# 03_ICs.net
KiCad netlist of a schematic drawn in Altium Designer
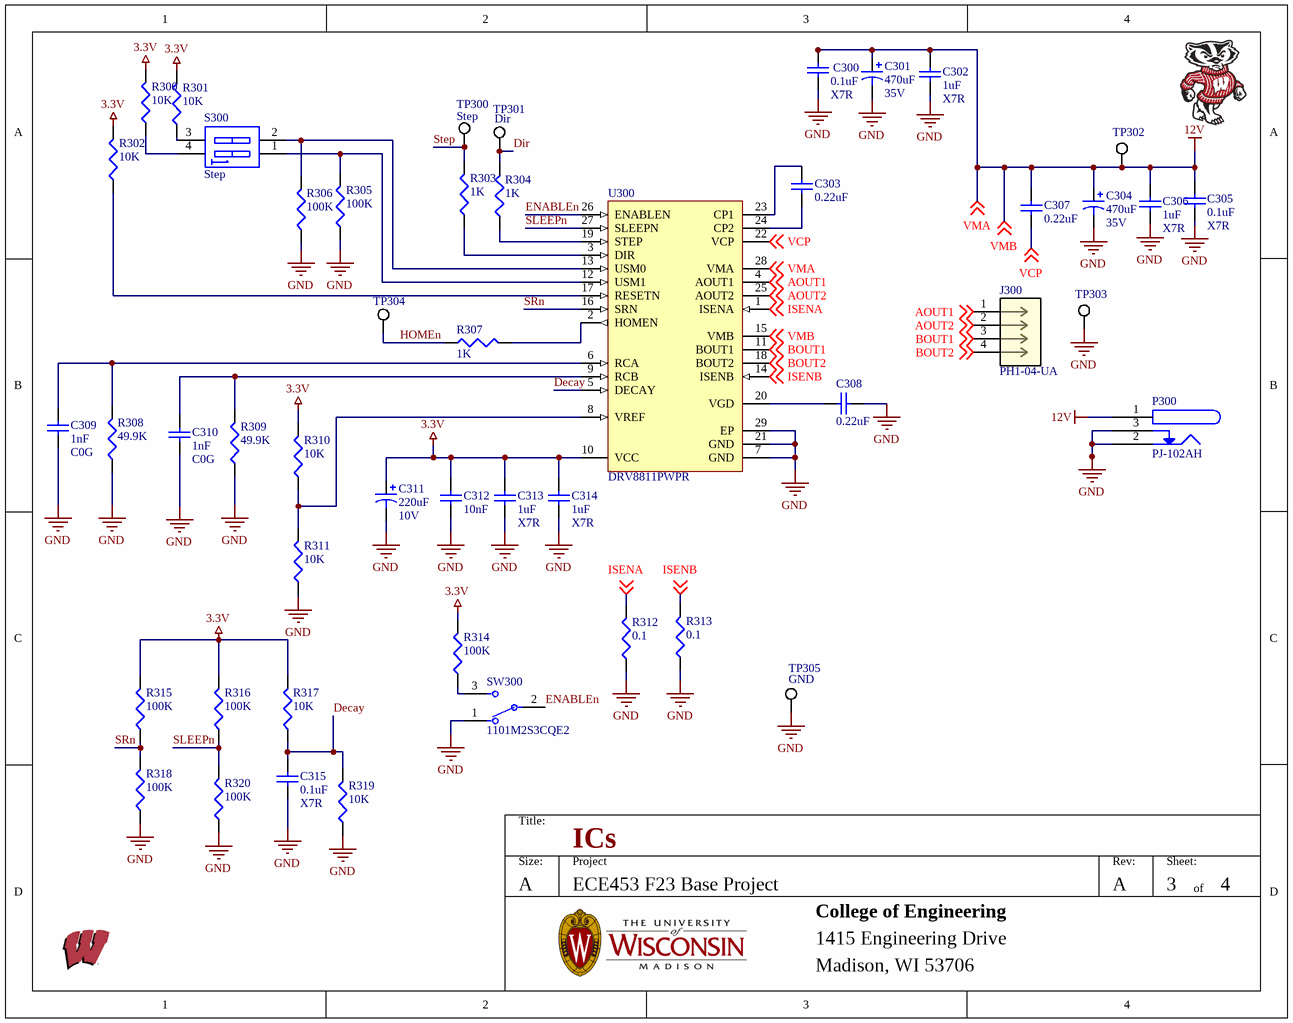
[diagram p0: 03_ICs.SchDoc]

(export (version "E")
  (design (tool "Eeschema 10.0.6"))
  (components
    (comp (ref "C300")
      (value "0.1uF")
      (footprint "CAPC2012M")
      (description "Cap Ceramic 0.1uF 50V X7R 20% SMD 0805 125°C Plastic T/R")
      (fields
        (field (name "MANUFACTURER") "KEMET")
        (field (name "MANUFACTURER PART NUMBER") "C0805C104M5RAC7210")
        (field (name "DIELECTRIC") "X7R")
      )
      (libsource (lib "ECE453") (part "Cap_1"))
    )
    (comp (ref "C301")
      (value "470uF")
      (footprint "CAPPR5-10x12.5")
      (description "CAP ALUM 470UF 20% 35V RADIAL")
      (fields
        (field (name "VOLTAGE") "35V")
        (field (name "MANUFACTURER") "Rubycon")
        (field (name "TOLERANCE") "20%")
      )
      (libsource (lib "ECE453") (part "Cap Pol3_1"))
    )
    (comp (ref "C302")
      (value "1uF")
      (footprint "CAPC2012M")
      (description "CAP CER 1UF 50V X7R 0805")
      (fields
        (field (name "MANUFACTURER") "Samsung")
        (field (name "MANUFACTURER PART NUMBER") "CL21B105KBFNNNE")
        (field (name "DIELECTRIC") "X7R")
      )
      (libsource (lib "ECE453") (part "Cap"))
    )
    (comp (ref "C303")
      (value "0.22uF")
      (footprint "CAP_0805")
      (description "Cap Ceramic 0.22uF 50V X7R 10% SMD 0805 125°C Plastic T/R")
      (fields
        (field (name "MANUFACTURER") "KEMET")
        (field (name "MANUFACTURER PART NUMBER") "C0805C224K5RACAUTO7210")
      )
      (libsource (lib "ECE453") (part "Cap_2"))
    )
    (comp (ref "C304")
      (value "470uF")
      (footprint "CAPPR5-10x12.5")
      (description "CAP ALUM 470UF 20% 35V RADIAL")
      (fields
        (field (name "VOLTAGE") "35V")
        (field (name "MANUFACTURER") "Rubycon")
        (field (name "TOLERANCE") "20%")
      )
      (libsource (lib "ECE453") (part "Cap Pol3_1"))
    )
    (comp (ref "C305")
      (value "0.1uF")
      (footprint "CAPC2012M")
      (description "Cap Ceramic 0.1uF 50V X7R 20% SMD 0805 125°C Plastic T/R")
      (fields
        (field (name "MANUFACTURER") "KEMET")
        (field (name "MANUFACTURER PART NUMBER") "C0805C104M5RAC7210")
        (field (name "DIELECTRIC") "X7R")
      )
      (libsource (lib "ECE453") (part "Cap_1"))
    )
    (comp (ref "C306")
      (value "1uF")
      (footprint "CAPC2012M")
      (description "CAP CER 1UF 50V X7R 0805")
      (fields
        (field (name "MANUFACTURER") "Samsung")
        (field (name "MANUFACTURER PART NUMBER") "CL21B105KBFNNNE")
        (field (name "DIELECTRIC") "X7R")
      )
      (libsource (lib "ECE453") (part "Cap"))
    )
    (comp (ref "C307")
      (value "0.22uF")
      (footprint "CAPC2012M")
      (description "Cap Ceramic 0.22uF 50V X7R 10% SMD 0805 125°C Plastic T/R")
      (fields
        (field (name "MANUFACTURER") "KEMET")
        (field (name "MANUFACTURER PART NUMBER") "C0805C224K5RACAUTO7210")
      )
      (libsource (lib "ECE453") (part "Cap_2"))
    )
    (comp (ref "C308")
      (value "0.22uF")
      (footprint "CAP_0805")
      (description "Cap Ceramic 0.22uF 50V X7R 10% SMD 0805 125°C Plastic T/R")
      (fields
        (field (name "MANUFACTURER") "KEMET")
        (field (name "MANUFACTURER PART NUMBER") "C0805C224K5RACAUTO7210")
      )
      (libsource (lib "ECE453") (part "Cap_2"))
    )
    (comp (ref "C309")
      (value "1nF")
      (footprint "CAP_0805")
      (description "Cap Ceramic 0.001uF 50V C0G 5% SMD 0805 125°C Punched Paper T/R")
      (fields
        (field (name "MANUFACTURER") "KEMET")
        (field (name "MANUFACTURER PART NUMBER") "C0805C102J5GAC7210")
        (field (name "DIELECTRIC") "C0G")
      )
      (libsource (lib "ECE453") (part "Cap_3"))
    )
    (comp (ref "C310")
      (value "1nF")
      (footprint "CAP_0805")
      (description "Cap Ceramic 0.001uF 50V C0G 5% SMD 0805 125°C Punched Paper T/R")
      (fields
        (field (name "MANUFACTURER") "KEMET")
        (field (name "MANUFACTURER PART NUMBER") "C0805C102J5GAC7210")
        (field (name "DIELECTRIC") "C0G")
      )
      (libsource (lib "ECE453") (part "Cap_3"))
    )
    (comp (ref "C311")
      (value "220uF")
      (footprint "CAPPR2-5x11")
      (description "Capacitor Al 105deg 220uF 10V 5X11")
      (fields
        (field (name "MANUFACTURER") "Rubycon")
        (field (name "MANUFACTURER PART NUMBER") "10YXJ220M5X11")
        (field (name "VOLTAGE") "10V")
      )
      (libsource (lib "ECE453") (part "Cap Pol1_1"))
    )
    (comp (ref "C312")
      (value "10nF")
      (footprint "CAP_0805")
      (description "Cap Ceramic 0.01uF 100V X7R 10% SMD 0805 125°C Plastic T/R")
      (fields
        (field (name "MANUFACTURER") "KEMET")
        (field (name "MANUFACTURER PART NUMBER") "C0805C103K1RAC7210")
      )
      (libsource (lib "ECE453") (part "Cap_4"))
    )
    (comp (ref "C313")
      (value "1uF")
      (footprint "CAPC2012M")
      (description "CAP CER 1UF 50V X7R 0805")
      (fields
        (field (name "MANUFACTURER") "Samsung")
        (field (name "MANUFACTURER PART NUMBER") "CL21B105KBFNNNE")
        (field (name "DIELECTRIC") "X7R")
      )
      (libsource (lib "ECE453") (part "Cap"))
    )
    (comp (ref "C314")
      (value "1uF")
      (footprint "CAPC2012M")
      (description "CAP CER 1UF 50V X7R 0805")
      (fields
        (field (name "MANUFACTURER") "Samsung")
        (field (name "MANUFACTURER PART NUMBER") "CL21B105KBFNNNE")
        (field (name "DIELECTRIC") "X7R")
      )
      (libsource (lib "ECE453") (part "Cap"))
    )
    (comp (ref "C315")
      (value "0.1uF")
      (footprint "CAPC2012M")
      (description "Cap Ceramic 0.1uF 50V X7R 20% SMD 0805 125°C Plastic T/R")
      (fields
        (field (name "MANUFACTURER") "KEMET")
        (field (name "MANUFACTURER PART NUMBER") "C0805C104M5RAC7210")
        (field (name "DIELECTRIC") "X7R")
      )
      (libsource (lib "ECE453") (part "Cap_1"))
    )
    (comp (ref "J300")
      (value "PH1-04-UA")
      (footprint "CONN_PH1-04-UA_ADM")
      (description "No Description Available")
      (fields (field (name "COPYRIGHT") "Copyright (C) 2023 Ultra Librarian. All rights reserved."))
      (libsource (lib "PH1-04-UA") (part "PH1-04-UA"))
    )
    (comp (ref "P300")
      (value "PJ-102")
      (footprint "PJ-102")
      (description "CONN PWR JACK 2.1X5.5MM HIGH CUR")
      (fields (field (name "MANUFACTURER") "CUI Inc") (field (name "MANUFACTURER PART NUMBER") "PJ-102AH"))
      (libsource (lib "ECE453") (part "CONN JACK PWR W/SW"))
    )
    (comp (ref "R300")
      (value "10K")
      (footprint "RES_0805")
      (description "Res Thick Film 0805 10K Ohm 1% 0.125W ±100ppm/°C Molded SMD Paper T/R")
      (fields
        (field (name "MANUFACTURER") "Stackpole Electronics")
        (field (name "MANUFACTURER PART NUMBER") "RMCF0805FT10K0")
      )
      (libsource (lib "ECE453") (part "Res3"))
    )
    (comp (ref "R301")
      (value "10K")
      (footprint "RES_0805")
      (description "Res Thick Film 0805 10K Ohm 1% 0.125W ±100ppm/°C Molded SMD Paper T/R")
      (fields
        (field (name "MANUFACTURER") "Stackpole Electronics")
        (field (name "MANUFACTURER PART NUMBER") "RMCF0805FT10K0")
      )
      (libsource (lib "ECE453") (part "Res3"))
    )
    (comp (ref "R302")
      (value "10K")
      (footprint "RES_0805")
      (description "Res Thick Film 0805 10K Ohm 1% 0.125W ±100ppm/°C Molded SMD Paper T/R")
      (fields
        (field (name "MANUFACTURER") "Stackpole Electronics")
        (field (name "MANUFACTURER PART NUMBER") "RMCF0805FT10K0")
      )
      (libsource (lib "ECE453") (part "Res3"))
    )
    (comp (ref "R303")
      (value "1K")
      (footprint "ECE453:RES_0805")
      (description "Res Thick Film 0805 1K Ohm 1% 0.125W(1/8W) ±100ppm/C Pad SMD Automotive T/R")
      (fields
        (field (name "MANUFACTURER") "Stackpole Electronics")
        (field (name "MANUFACTURER PART NUMBER") "RMCF0805FT1K00")
      )
      (libsource (lib "ECE453") (part "Res3_1"))
    )
    (comp (ref "R304")
      (value "1K")
      (footprint "ECE453:RES_0805")
      (description "Res Thick Film 0805 1K Ohm 1% 0.125W(1/8W) ±100ppm/C Pad SMD Automotive T/R")
      (fields
        (field (name "MANUFACTURER") "Stackpole Electronics")
        (field (name "MANUFACTURER PART NUMBER") "RMCF0805FT1K00")
      )
      (libsource (lib "ECE453") (part "Res3_1"))
    )
    (comp (ref "R305")
      (value "100K")
      (footprint "RES_0805")
      (description "Res Thick Film 0805 100K Ohm 1% 0.125W ±100ppm/°C Molded SMD Paper T/R")
      (fields
        (field (name "MANUFACTURER") "Stackpole Electronics")
        (field (name "MANUFACTURER PART NUMBER") "RMCF0805FT100K")
      )
      (libsource (lib "ECE453") (part "Res3_4"))
    )
    (comp (ref "R306")
      (value "100K")
      (footprint "RES_0805")
      (description "Res Thick Film 0805 100K Ohm 1% 0.125W ±100ppm/°C Molded SMD Paper T/R")
      (fields
        (field (name "MANUFACTURER") "Stackpole Electronics")
        (field (name "MANUFACTURER PART NUMBER") "RMCF0805FT100K")
      )
      (libsource (lib "ECE453") (part "Res3_4"))
    )
    (comp (ref "R307")
      (value "1K")
      (footprint "ECE453:RES_0805")
      (description "Res Thick Film 0805 1K Ohm 1% 0.125W(1/8W) ±100ppm/C Pad SMD Automotive T/R")
      (fields
        (field (name "MANUFACTURER") "Stackpole Electronics")
        (field (name "MANUFACTURER PART NUMBER") "RMCF0805FT1K00")
      )
      (libsource (lib "ECE453") (part "Res3_1"))
    )
    (comp (ref "R308")
      (value "49.9K")
      (footprint "RES_0805")
      (description "Res Thick Film 0805 49.9K Ohm 1% 0.125W ±100ppm/°C Molded SMD Paper T/R")
      (fields
        (field (name "MANUFACTURER") "Stackpole Electronics")
        (field (name "MANUFACTURER PART NUMBER") "RMCF0805FT49K9")
      )
      (libsource (lib "ECE453") (part "Res3_3"))
    )
    (comp (ref "R309")
      (value "49.9K")
      (footprint "RES_0805")
      (description "Res Thick Film 0805 49.9K Ohm 1% 0.125W ±100ppm/°C Molded SMD Paper T/R")
      (fields
        (field (name "MANUFACTURER") "Stackpole Electronics")
        (field (name "MANUFACTURER PART NUMBER") "RMCF0805FT49K9")
      )
      (libsource (lib "ECE453") (part "Res3_3"))
    )
    (comp (ref "R310")
      (value "10K")
      (footprint "RES_0805")
      (description "Res Thick Film 0805 10K Ohm 1% 0.125W ±100ppm/°C Molded SMD Paper T/R")
      (fields
        (field (name "MANUFACTURER") "Stackpole Electronics")
        (field (name "MANUFACTURER PART NUMBER") "RMCF0805FT10K0")
      )
      (libsource (lib "ECE453") (part "Res3"))
    )
    (comp (ref "R311")
      (value "10K")
      (footprint "RES_0805")
      (description "Res Thick Film 0805 10K Ohm 1% 0.125W ±100ppm/°C Molded SMD Paper T/R")
      (fields
        (field (name "MANUFACTURER") "Stackpole Electronics")
        (field (name "MANUFACTURER PART NUMBER") "RMCF0805FT10K0")
      )
      (libsource (lib "ECE453") (part "Res3"))
    )
    (comp (ref "R312")
      (value "0.1")
      (footprint "RES_0805")
      (description "Res 0.1 Ohm 1% 1W 1206")
      (fields
        (field (name "MANUFACTURER") "Cyntec")
        (field (name "MANUFACTURER PART NUMBER") "SCRR1206S1-R100F")
      )
      (libsource (lib "ECE453") (part "Res3_2"))
    )
    (comp (ref "R313")
      (value "0.1")
      (footprint "RES_0805")
      (description "Res 0.1 Ohm 1% 1W 1206")
      (fields
        (field (name "MANUFACTURER") "Cyntec")
        (field (name "MANUFACTURER PART NUMBER") "SCRR1206S1-R100F")
      )
      (libsource (lib "ECE453") (part "Res3_2"))
    )
    (comp (ref "R314")
      (value "100K")
      (footprint "RES_0805")
      (description "Res Thick Film 0805 100K Ohm 1% 0.125W ±100ppm/°C Molded SMD Paper T/R")
      (fields
        (field (name "MANUFACTURER") "Stackpole Electronics")
        (field (name "MANUFACTURER PART NUMBER") "RMCF0805FT100K")
      )
      (libsource (lib "ECE453") (part "Res3_4"))
    )
    (comp (ref "R315")
      (value "100K")
      (footprint "RES_0805")
      (description "Res Thick Film 0805 100K Ohm 1% 0.125W ±100ppm/°C Molded SMD Paper T/R")
      (fields
        (field (name "MANUFACTURER") "Stackpole Electronics")
        (field (name "MANUFACTURER PART NUMBER") "RMCF0805FT100K")
      )
      (libsource (lib "ECE453") (part "Res3_4"))
    )
    (comp (ref "R316")
      (value "100K")
      (footprint "RES_0805")
      (description "Res Thick Film 0805 100K Ohm 1% 0.125W ±100ppm/°C Molded SMD Paper T/R")
      (fields
        (field (name "MANUFACTURER") "Stackpole Electronics")
        (field (name "MANUFACTURER PART NUMBER") "RMCF0805FT100K")
      )
      (libsource (lib "ECE453") (part "Res3_4"))
    )
    (comp (ref "R317")
      (value "10K")
      (footprint "RES_0805")
      (description "Res Thick Film 0805 10K Ohm 1% 0.125W ±100ppm/°C Molded SMD Paper T/R")
      (fields
        (field (name "MANUFACTURER") "Stackpole Electronics")
        (field (name "MANUFACTURER PART NUMBER") "RMCF0805FT10K0")
      )
      (libsource (lib "ECE453") (part "Res3"))
    )
    (comp (ref "R318")
      (value "100K")
      (footprint "RES_0805")
      (description "Res Thick Film 0805 100K Ohm 1% 0.125W ±100ppm/°C Molded SMD Paper T/R")
      (fields
        (field (name "MANUFACTURER") "Stackpole Electronics")
        (field (name "MANUFACTURER PART NUMBER") "RMCF0805FT100K")
      )
      (libsource (lib "ECE453") (part "Res3_4"))
    )
    (comp (ref "R319")
      (value "10K")
      (footprint "RES_0805")
      (description "Res Thick Film 0805 10K Ohm 1% 0.125W ±100ppm/°C Molded SMD Paper T/R")
      (fields
        (field (name "MANUFACTURER") "Stackpole Electronics")
        (field (name "MANUFACTURER PART NUMBER") "RMCF0805FT10K0")
      )
      (libsource (lib "ECE453") (part "Res3"))
    )
    (comp (ref "R320")
      (value "100K")
      (footprint "RES_0805")
      (description "Res Thick Film 0805 100K Ohm 1% 0.125W ±100ppm/°C Molded SMD Paper T/R")
      (fields
        (field (name "MANUFACTURER") "Stackpole Electronics")
        (field (name "MANUFACTURER PART NUMBER") "RMCF0805FT100K")
      )
      (libsource (lib "ECE453") (part "Res3_4"))
    )
    (comp (ref "S300")
      (value "Step")
      (footprint "DIP-4")
      (description "Switch DIP OFF ON SPST 2 Raised Slide 0.025A 24VDC PC Pins 2.54mm Thru-Hole Tube")
      (fields
        (field (name "MANUFACTURER") "CUI Devices")
        (field (name "MANUFACTURER PART NUMBER") "DS01-254-L-02BE")
      )
      (libsource (lib "ECE453") (part "SW DIP-2"))
    )
    (comp (ref "SW300")
      (value "1101M2S3CQE2")
      (footprint "FP-1101M2S3CQE2-MFG")
      (description "SWITCH SLIDE SPDT 6A 120V")
      (libsource (lib "Altium Content Vault") (part "7fcaa069a19c2acd609832313418d7c"))
    )
    (comp (ref "TP300")
      (value "Step")
      (footprint "KSTN-5019_V")
      (description "Test Point, 1 Position SMD, RoHS, Tape and Reel")
      (fields
        (field (name "MANUFACTURER") "Keystone Electronics")
        (field (name "MANUFACTURER PART NUMBER") "5019")
      )
      (libsource (lib "ECE453") (part "CMP-1672-00008-1"))
    )
    (comp (ref "TP301")
      (value "Dir")
      (footprint "KSTN-5019_V")
      (description "Test Point, 1 Position SMD, RoHS, Tape and Reel")
      (fields
        (field (name "MANUFACTURER") "Keystone Electronics")
        (field (name "MANUFACTURER PART NUMBER") "5019")
      )
      (libsource (lib "ECE453") (part "CMP-1672-00008-1"))
    )
    (comp (ref "TP302")
      (value "5019")
      (footprint "KSTN-5019_V")
      (description "Test Point, 1 Position SMD, RoHS, Tape and Reel")
      (fields (field (name "MANUFACTURER") "Keystone Electronics"))
      (libsource (lib "ECE453") (part "CMP-1672-00008-1"))
    )
    (comp (ref "TP303")
      (value "5019")
      (footprint "KSTN-5019_V")
      (description "Test Point, 1 Position SMD, RoHS, Tape and Reel")
      (fields (field (name "MANUFACTURER") "Keystone Electronics"))
      (libsource (lib "ECE453") (part "CMP-1672-00008-1"))
    )
    (comp (ref "TP304")
      (value "5019")
      (footprint "KSTN-5019_V")
      (description "Test Point, 1 Position SMD, RoHS, Tape and Reel")
      (fields (field (name "MANUFACTURER") "Keystone Electronics"))
      (libsource (lib "ECE453") (part "CMP-1672-00008-1"))
    )
    (comp (ref "TP305")
      (value "GND")
      (footprint "KSTN-5019_V")
      (description "Test Point, 1 Position SMD, RoHS, Tape and Reel")
      (fields
        (field (name "MANUFACTURER") "Keystone Electronics")
        (field (name "MANUFACTURER PART NUMBER") "5019")
      )
      (libsource (lib "ECE453") (part "CMP-1672-00008-1"))
    )
    (comp (ref "U300")
      (value "DRV8811PWPR")
      (footprint "PWP0028C_M")
      (libsource (lib "Altium Content Vault") (part "TI-DRV8811PWP28-5230X2750TP"))
    )
  )
  (nets
    (net (code "1") (name "/Decay") (class "Default")
      (node (ref "C315") (pin "2") (pinfunction "2_2") (pintype "passive"))
      (node (ref "R317") (pin "1") (pinfunction "1_1") (pintype "passive"))
      (node (ref "R319") (pin "2") (pinfunction "2_2") (pintype "passive"))
      (node (ref "U300") (pin "5") (pinfunction "DECAY_5") (pintype "input"))
    )
    (net (code "2") (name "/Dir") (class "Default")
      (node (ref "R304") (pin "2") (pinfunction "2_2") (pintype "passive"))
      (node (ref "TP301") (pin "1") (pinfunction "1_1") (pintype "passive"))
    )
    (net (code "3") (name "/ENABLEn") (class "Default")
      (node (ref "SW300") (pin "2") (pinfunction "COMM_2") (pintype "passive"))
      (node (ref "U300") (pin "26") (pinfunction "ENABLEN_26") (pintype "input"))
    )
    (net (code "4") (name "/HOMEn") (class "Default")
      (node (ref "R307") (pin "1") (pinfunction "1_1") (pintype "passive"))
      (node (ref "TP304") (pin "1") (pinfunction "1_1") (pintype "passive"))
    )
    (net (code "5") (name "/SLEEPn") (class "Default")
      (node (ref "R316") (pin "1") (pinfunction "1_1") (pintype "passive"))
      (node (ref "R320") (pin "2") (pinfunction "2_2") (pintype "passive"))
      (node (ref "U300") (pin "27") (pinfunction "SLEEPN_27") (pintype "input"))
    )
    (net (code "6") (name "/SRn") (class "Default")
      (node (ref "R315") (pin "1") (pinfunction "1_1") (pintype "passive"))
      (node (ref "R318") (pin "2") (pinfunction "2_2") (pintype "passive"))
      (node (ref "U300") (pin "16") (pinfunction "SRN_16") (pintype "input"))
    )
    (net (code "7") (name "/Step") (class "Default")
      (node (ref "R303") (pin "2") (pinfunction "2_2") (pintype "passive"))
      (node (ref "TP300") (pin "1") (pinfunction "1_1") (pintype "passive"))
    )
    (net (code "8") (name "3.3V") (class "Default")
      (node (ref "C311") (pin "1") (pinfunction "1_1") (pintype "passive"))
      (node (ref "C312") (pin "2") (pinfunction "2_2") (pintype "passive"))
      (node (ref "C313") (pin "2") (pinfunction "2_2") (pintype "passive"))
      (node (ref "C314") (pin "2") (pinfunction "2_2") (pintype "passive"))
      (node (ref "R300") (pin "2") (pinfunction "2_2") (pintype "passive"))
      (node (ref "R301") (pin "2") (pinfunction "2_2") (pintype "passive"))
      (node (ref "R302") (pin "2") (pinfunction "2_2") (pintype "passive"))
      (node (ref "R310") (pin "2") (pinfunction "2_2") (pintype "passive"))
      (node (ref "R314") (pin "2") (pinfunction "2_2") (pintype "passive"))
      (node (ref "R315") (pin "2") (pinfunction "2_2") (pintype "passive"))
      (node (ref "R316") (pin "2") (pinfunction "2_2") (pintype "passive"))
      (node (ref "R317") (pin "2") (pinfunction "2_2") (pintype "passive"))
      (node (ref "U300") (pin "10") (pinfunction "VCC_10") (pintype "power_in"))
    )
    (net (code "9") (name "12V") (class "Default")
      (node (ref "C300") (pin "2") (pinfunction "2_2") (pintype "passive"))
      (node (ref "C301") (pin "1") (pinfunction "1_1") (pintype "passive"))
      (node (ref "C302") (pin "2") (pinfunction "2_2") (pintype "passive"))
      (node (ref "C304") (pin "1") (pinfunction "1_1") (pintype "passive"))
      (node (ref "C305") (pin "2") (pinfunction "2_2") (pintype "passive"))
      (node (ref "C306") (pin "2") (pinfunction "2_2") (pintype "passive"))
      (node (ref "C307") (pin "2") (pinfunction "2_2") (pintype "passive"))
      (node (ref "P300") (pin "1") (pinfunction "1_1") (pintype "passive"))
      (node (ref "TP302") (pin "1") (pinfunction "1_1") (pintype "passive"))
      (node (ref "U300") (pin "15") (pinfunction "VMB_15") (pintype "power_in"))
      (node (ref "U300") (pin "28") (pinfunction "VMA_28") (pintype "power_in"))
    )
    (net (code "10") (name "AOUT1") (class "Default")
      (node (ref "J300") (pin "1") (pinfunction "1_1") (pintype "passive"))
      (node (ref "U300") (pin "4") (pinfunction "AOUT1_4") (pintype "power_in"))
    )
    (net (code "11") (name "AOUT2") (class "Default")
      (node (ref "J300") (pin "2") (pinfunction "2_2") (pintype "passive"))
      (node (ref "U300") (pin "25") (pinfunction "AOUT2_25") (pintype "power_in"))
    )
    (net (code "12") (name "BOUT1") (class "Default")
      (node (ref "J300") (pin "3") (pinfunction "3_3") (pintype "passive"))
      (node (ref "U300") (pin "11") (pinfunction "BOUT1_11") (pintype "power_in"))
    )
    (net (code "13") (name "BOUT2") (class "Default")
      (node (ref "J300") (pin "4") (pinfunction "4_4") (pintype "passive"))
      (node (ref "U300") (pin "18") (pinfunction "BOUT2_18") (pintype "power_in"))
    )
    (net (code "14") (name "GND") (class "Default")
      (node (ref "C300") (pin "1") (pinfunction "1_1") (pintype "passive"))
      (node (ref "C301") (pin "2") (pinfunction "2_2") (pintype "passive"))
      (node (ref "C302") (pin "1") (pinfunction "1_1") (pintype "passive"))
      (node (ref "C304") (pin "2") (pinfunction "2_2") (pintype "passive"))
      (node (ref "C305") (pin "1") (pinfunction "1_1") (pintype "passive"))
      (node (ref "C306") (pin "1") (pinfunction "1_1") (pintype "passive"))
      (node (ref "C308") (pin "2") (pinfunction "2_2") (pintype "passive"))
      (node (ref "C309") (pin "1") (pinfunction "1_1") (pintype "passive"))
      (node (ref "C310") (pin "1") (pinfunction "1_1") (pintype "passive"))
      (node (ref "C311") (pin "2") (pinfunction "2_2") (pintype "passive"))
      (node (ref "C312") (pin "1") (pinfunction "1_1") (pintype "passive"))
      (node (ref "C313") (pin "1") (pinfunction "1_1") (pintype "passive"))
      (node (ref "C314") (pin "1") (pinfunction "1_1") (pintype "passive"))
      (node (ref "C315") (pin "1") (pinfunction "1_1") (pintype "passive"))
      (node (ref "P300") (pin "2") (pinfunction "2_2") (pintype "passive"))
      (node (ref "P300") (pin "3") (pinfunction "3_3") (pintype "passive"))
      (node (ref "R305") (pin "1") (pinfunction "1_1") (pintype "passive"))
      (node (ref "R306") (pin "1") (pinfunction "1_1") (pintype "passive"))
      (node (ref "R308") (pin "1") (pinfunction "1_1") (pintype "passive"))
      (node (ref "R309") (pin "1") (pinfunction "1_1") (pintype "passive"))
      (node (ref "R311") (pin "1") (pinfunction "1_1") (pintype "passive"))
      (node (ref "R312") (pin "1") (pinfunction "1_1") (pintype "passive"))
      (node (ref "R313") (pin "1") (pinfunction "1_1") (pintype "passive"))
      (node (ref "R318") (pin "1") (pinfunction "1_1") (pintype "passive"))
      (node (ref "R319") (pin "1") (pinfunction "1_1") (pintype "passive"))
      (node (ref "R320") (pin "1") (pinfunction "1_1") (pintype "passive"))
      (node (ref "SW300") (pin "1") (pinfunction "1_1") (pintype "passive"))
      (node (ref "TP303") (pin "1") (pinfunction "1_1") (pintype "passive"))
      (node (ref "TP305") (pin "1") (pinfunction "1_1") (pintype "passive"))
      (node (ref "U300") (pin "21") (pinfunction "GND_21") (pintype "power_in"))
      (node (ref "U300") (pin "29") (pinfunction "EP_29") (pintype "power_in"))
      (node (ref "U300") (pin "7") (pinfunction "GND_7") (pintype "power_in"))
    )
    (net (code "15") (name "ISENA") (class "Default")
      (node (ref "R312") (pin "2") (pinfunction "2_2") (pintype "passive"))
      (node (ref "U300") (pin "1") (pinfunction "ISENA_1") (pintype "input"))
    )
    (net (code "16") (name "ISENB") (class "Default")
      (node (ref "R313") (pin "2") (pinfunction "2_2") (pintype "passive"))
      (node (ref "U300") (pin "14") (pinfunction "ISENB_14") (pintype "input"))
    )
    (net (code "17") (name "Net-(R314-Pad1)") (class "Default")
      (node (ref "R314") (pin "1") (pinfunction "1_1") (pintype "passive"))
      (node (ref "SW300") (pin "3") (pinfunction "3_3") (pintype "passive"))
    )
    (net (code "18") (name "Net-(S300-A1)") (class "Default")
      (node (ref "R305") (pin "2") (pinfunction "2_2") (pintype "passive"))
      (node (ref "S300") (pin "1") (pinfunction "A1_1") (pintype "passive"))
      (node (ref "U300") (pin "12") (pinfunction "USM1_12") (pintype "input"))
    )
    (net (code "19") (name "Net-(S300-A2)") (class "Default")
      (node (ref "R306") (pin "2") (pinfunction "2_2") (pintype "passive"))
      (node (ref "S300") (pin "2") (pinfunction "A2_2") (pintype "passive"))
      (node (ref "U300") (pin "13") (pinfunction "USM0_13") (pintype "input"))
    )
    (net (code "20") (name "Net-(S300-B1)") (class "Default")
      (node (ref "R300") (pin "1") (pinfunction "1_1") (pintype "passive"))
      (node (ref "S300") (pin "4") (pinfunction "B1_4") (pintype "passive"))
    )
    (net (code "21") (name "Net-(S300-B2)") (class "Default")
      (node (ref "R301") (pin "1") (pinfunction "1_1") (pintype "passive"))
      (node (ref "S300") (pin "3") (pinfunction "B2_3") (pintype "passive"))
    )
    (net (code "22") (name "Net-(U300-CP1)") (class "Default")
      (node (ref "C303") (pin "2") (pinfunction "2_2") (pintype "passive"))
      (node (ref "U300") (pin "23") (pinfunction "CP1_23") (pintype "passive"))
    )
    (net (code "23") (name "Net-(U300-CP2)") (class "Default")
      (node (ref "C303") (pin "1") (pinfunction "1_1") (pintype "passive"))
      (node (ref "U300") (pin "24") (pinfunction "CP2_24") (pintype "passive"))
    )
    (net (code "24") (name "Net-(U300-DIR)") (class "Default")
      (node (ref "R303") (pin "1") (pinfunction "1_1") (pintype "passive"))
      (node (ref "U300") (pin "3") (pinfunction "DIR_3") (pintype "input"))
    )
    (net (code "25") (name "Net-(U300-HOMEN)") (class "Default")
      (node (ref "R307") (pin "2") (pinfunction "2_2") (pintype "passive"))
      (node (ref "U300") (pin "2") (pinfunction "HOMEN_2") (pintype "output"))
    )
    (net (code "26") (name "Net-(U300-RCA)") (class "Default")
      (node (ref "C309") (pin "2") (pinfunction "2_2") (pintype "passive"))
      (node (ref "R308") (pin "2") (pinfunction "2_2") (pintype "passive"))
      (node (ref "U300") (pin "6") (pinfunction "RCA_6") (pintype "input"))
    )
    (net (code "27") (name "Net-(U300-RCB)") (class "Default")
      (node (ref "C310") (pin "2") (pinfunction "2_2") (pintype "passive"))
      (node (ref "R309") (pin "2") (pinfunction "2_2") (pintype "passive"))
      (node (ref "U300") (pin "9") (pinfunction "RCB_9") (pintype "input"))
    )
    (net (code "28") (name "Net-(U300-RESETN)") (class "Default")
      (node (ref "R302") (pin "1") (pinfunction "1_1") (pintype "passive"))
      (node (ref "U300") (pin "17") (pinfunction "RESETN_17") (pintype "input"))
    )
    (net (code "29") (name "Net-(U300-STEP)") (class "Default")
      (node (ref "R304") (pin "1") (pinfunction "1_1") (pintype "passive"))
      (node (ref "U300") (pin "19") (pinfunction "STEP_19") (pintype "input"))
    )
    (net (code "30") (name "Net-(U300-VGD)") (class "Default")
      (node (ref "C308") (pin "1") (pinfunction "1_1") (pintype "passive"))
      (node (ref "U300") (pin "20") (pinfunction "VGD_20") (pintype "power_in"))
    )
    (net (code "31") (name "Net-(U300-VREF)") (class "Default")
      (node (ref "R310") (pin "1") (pinfunction "1_1") (pintype "passive"))
      (node (ref "R311") (pin "2") (pinfunction "2_2") (pintype "passive"))
      (node (ref "U300") (pin "8") (pinfunction "VREF_8") (pintype "input"))
    )
    (net (code "32") (name "VCP") (class "Default")
      (node (ref "C307") (pin "1") (pinfunction "1_1") (pintype "passive"))
      (node (ref "U300") (pin "22") (pinfunction "VCP_22") (pintype "power_in"))
    )
  )
)
